# Power_CAN_IO_GPS.net
KiCad netlist of a schematic drawn in Altium Designer
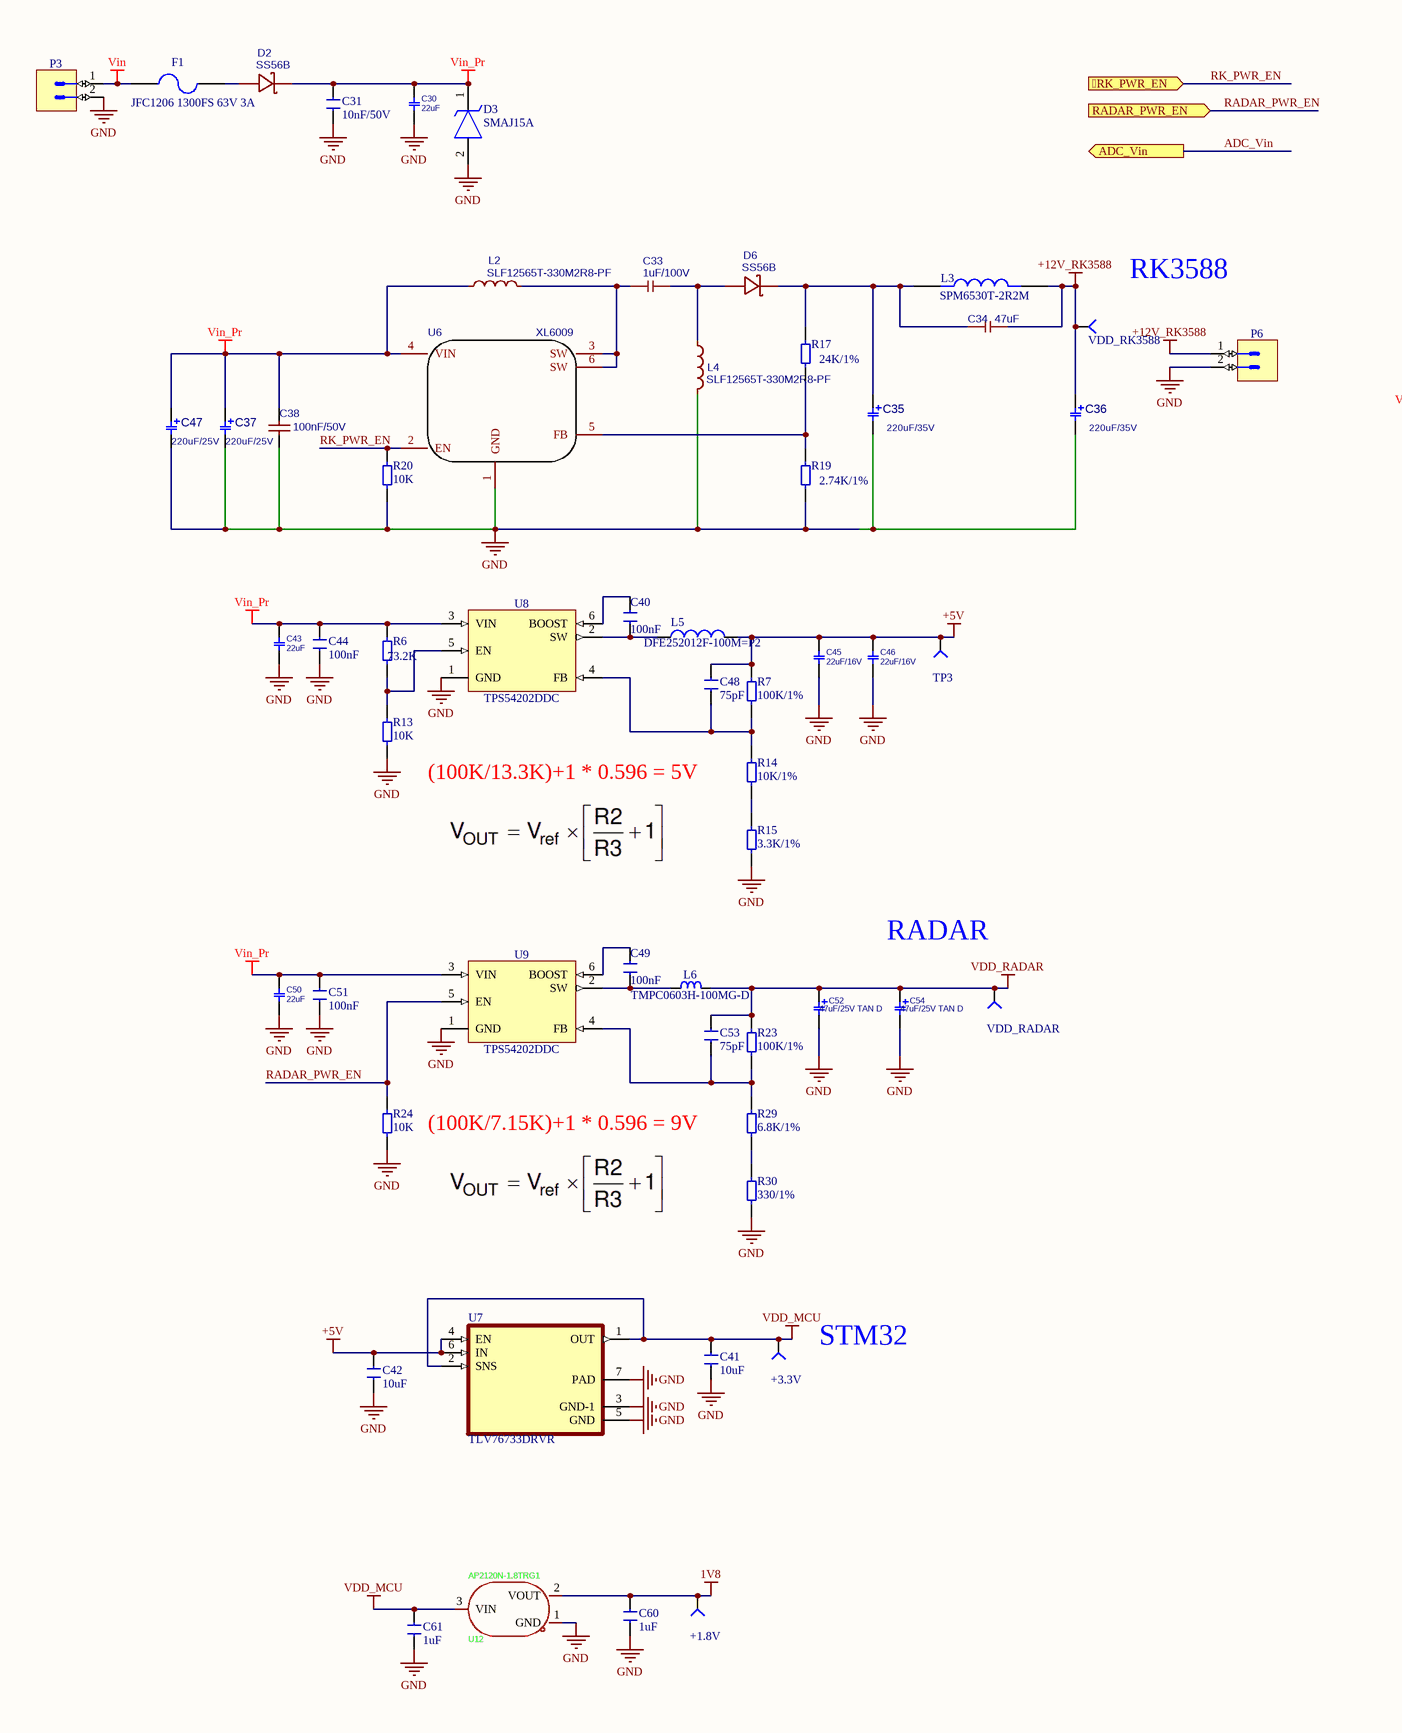
[diagram p0: Power_CAN_IO_GPS.SchDoc, left]
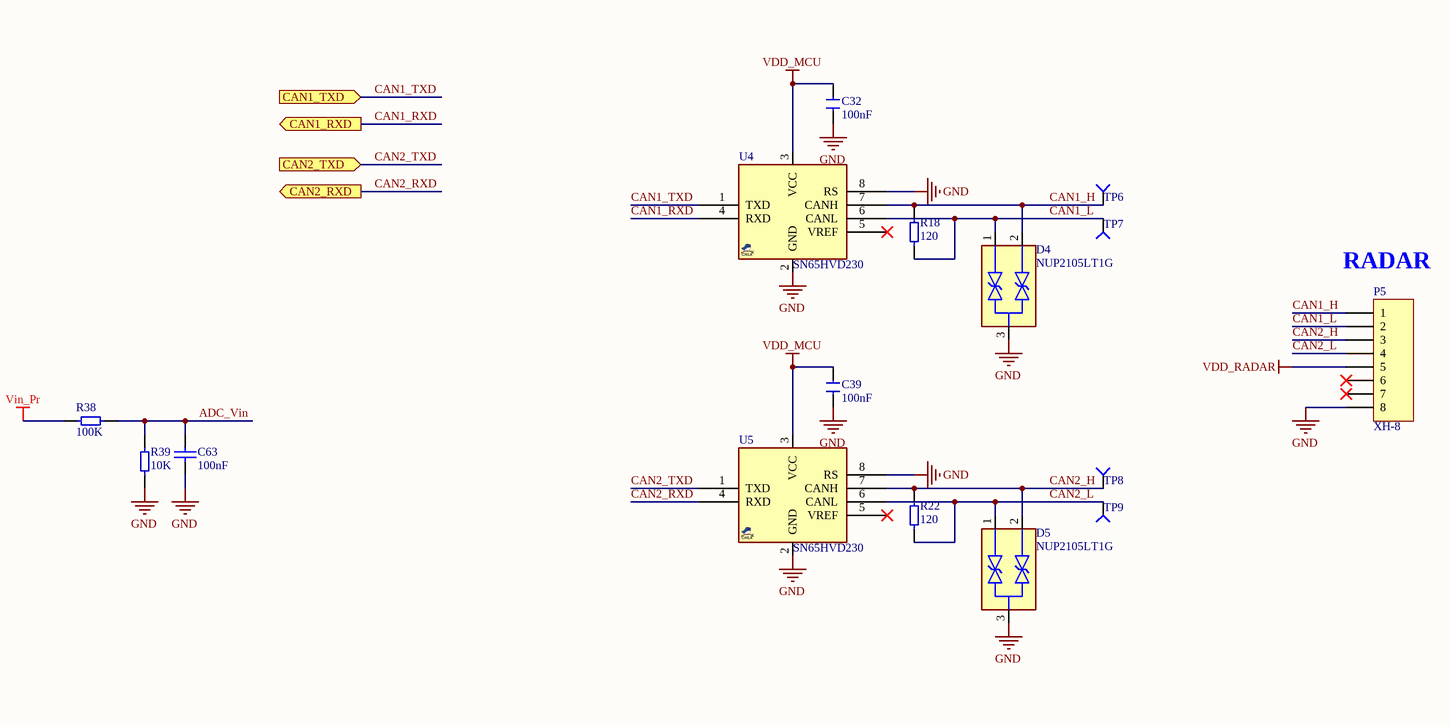
[diagram p1: Power_CAN_IO_GPS.SchDoc, right]

(export (version "E")
  (design (tool "Eeschema 10.0.6"))
  (components
    (comp (ref "+1.8V")
      (value "TEST POINT")
      (footprint "TEST_POINT")
      (libsource (lib "Tracker_MAIN_V1.01") (part "TEST POINT"))
    )
    (comp (ref "+3.3V")
      (value "TEST POINT")
      (footprint "TEST_POINT")
      (libsource (lib "Tracker_MAIN_V1.01") (part "TEST POINT"))
    )
    (comp (ref "C30")
      (value "22uF")
      (footprint "C1206E")
      (description "CAP, MLCC, X5R 22uF 25V 20% 1206")
      (fields (field (name "MANF_P#") "TMK316BBJ226ML-T") (field (name "MANF") "Taiyo Yuden"))
      (libsource (lib "mlcc_smd_passive") (part "CAP_SMD_MLCC_22u25V"))
    )
    (comp (ref "C31")
      (value "10nF/50V")
      (footprint "C0603E")
      (libsource (lib "Rahimi librery") (part "Capacitor SMD"))
    )
    (comp (ref "C32")
      (value "100nF")
      (footprint "C0603E")
      (libsource (lib "Rahimi librery") (part "Capacitor SMD"))
    )
    (comp (ref "C33")
      (value "1uF/100V")
      (footprint "C1210")
      (fields (field (name "MANUFACTURER PART") "GRM32ER71A476ME15L"))
      (libsource (lib "altium-import") (part "root_0_47uF_"))
    )
    (comp (ref "C34")
      (value "47uF")
      (footprint "C1210")
      (fields (field (name "MANUFACTURER PART") "GRM32ER71A476ME15L"))
      (libsource (lib "altium-import") (part "root_0_47uF_"))
    )
    (comp (ref "C35")
      (value "220uF/35V")
      (footprint "C_EL_D8L10")
      (description "CAP, SMD, ELEC,")
      (fields (field (name "MANF_P#") "MANF_PART#") (field (name "MANF") "MANF"))
      (libsource (lib "passive_smd") (part "CAP_SMD_EL_220uF_35v"))
    )
    (comp (ref "C36")
      (value "220uF/35V")
      (footprint "C_EL_D8L10")
      (description "CAP, SMD, ELEC,")
      (fields (field (name "MANF_P#") "MANF_PART#") (field (name "MANF") "MANF"))
      (libsource (lib "passive_smd") (part "CAP_SMD_EL_220uF_35v"))
    )
    (comp (ref "C37")
      (value "220uF/25V")
      (footprint "C_EL_D8L10")
      (description "CAP, SMD, ELEC,")
      (fields (field (name "MANF_P#") "MANF_PART#") (field (name "MANF") "MANF"))
      (libsource (lib "passive_smd") (part "CAP_SMD_EL_220uF_35v"))
    )
    (comp (ref "C38")
      (value "100nF/50V")
      (footprint "C0805")
      (fields (field (name "MANUFACTURER") "FH") (field (name "MANUFACTURER PART") "0805F224M500NT"))
      (libsource (lib "altium-import") (part "root_1_224_"))
    )
    (comp (ref "C39")
      (value "100nF")
      (footprint "C0603E")
      (libsource (lib "Rahimi librery") (part "Capacitor SMD"))
    )
    (comp (ref "C40")
      (value "100nF")
      (footprint "C0603E")
      (libsource (lib "Rahimi librery") (part "Capacitor SMD"))
    )
    (comp (ref "C41")
      (value "10uF")
      (footprint "C0603E")
      (libsource (lib "Rahimi librery") (part "Capacitor SMD"))
    )
    (comp (ref "C42")
      (value "10uF")
      (footprint "C0603E")
      (libsource (lib "Rahimi librery") (part "Capacitor SMD"))
    )
    (comp (ref "C43")
      (value "22uF")
      (footprint "C1206E")
      (description "CAP, MLCC, X5R 22uF 25V 20% 1206")
      (fields (field (name "MANF_P#") "TMK316BBJ226ML-T") (field (name "MANF") "Taiyo Yuden"))
      (libsource (lib "mlcc_smd_passive") (part "CAP_SMD_MLCC_22u25V"))
    )
    (comp (ref "C44")
      (value "100nF")
      (footprint "C0603E")
      (libsource (lib "Rahimi librery") (part "Capacitor SMD"))
    )
    (comp (ref "C45")
      (value "22uF/16V")
      (footprint "C1206E")
      (description "CAP, MLCC, X5R 22uF 25V 20% 1206")
      (fields (field (name "MANF_P#") "TMK316BBJ226ML-T") (field (name "MANF") "Taiyo Yuden"))
      (libsource (lib "mlcc_smd_passive") (part "CAP_SMD_MLCC_22u25V"))
    )
    (comp (ref "C46")
      (value "22uF/16V")
      (footprint "C1206E")
      (description "CAP, MLCC, X5R 22uF 25V 20% 1206")
      (fields (field (name "MANF_P#") "TMK316BBJ226ML-T") (field (name "MANF") "Taiyo Yuden"))
      (libsource (lib "mlcc_smd_passive") (part "CAP_SMD_MLCC_22u25V"))
    )
    (comp (ref "C47")
      (value "220uF/25V")
      (footprint "C_EL_D8L10")
      (description "CAP, SMD, ELEC,")
      (fields (field (name "MANF_P#") "MANF_PART#") (field (name "MANF") "MANF"))
      (libsource (lib "passive_smd") (part "CAP_SMD_EL_220uF_35v"))
    )
    (comp (ref "C48")
      (value "75pF")
      (footprint "C0603E")
      (libsource (lib "Rahimi librery") (part "Capacitor SMD"))
    )
    (comp (ref "C49")
      (value "100nF")
      (footprint "C0603E")
      (libsource (lib "Rahimi librery") (part "Capacitor SMD"))
    )
    (comp (ref "C50")
      (value "22uF")
      (footprint "C1206E")
      (description "CAP, MLCC, X5R 22uF 25V 20% 1206")
      (fields (field (name "MANF_P#") "TMK316BBJ226ML-T") (field (name "MANF") "Taiyo Yuden"))
      (libsource (lib "mlcc_smd_passive") (part "CAP_SMD_MLCC_22u25V"))
    )
    (comp (ref "C51")
      (value "100nF")
      (footprint "C0603E")
      (libsource (lib "Rahimi librery") (part "Capacitor SMD"))
    )
    (comp (ref "C52")
      (value "47uF/25V TAN D")
      (footprint "C_TN_7343")
      (description "CAP, SMD, TAN")
      (fields (field (name "MANF") "VISHAY") (field (name "MANF_P#") "T55A106M6R3C0300"))
      (libsource (lib "passive_smd") (part "CAP_SMD_TAN"))
    )
    (comp (ref "C53")
      (value "75pF")
      (footprint "C0603E")
      (libsource (lib "Rahimi librery") (part "Capacitor SMD"))
    )
    (comp (ref "C54")
      (value "47uF/25V TAN D")
      (footprint "C_TN_7343")
      (description "CAP, SMD, TAN")
      (fields (field (name "MANF") "VISHAY") (field (name "MANF_P#") "T55A106M6R3C0300"))
      (libsource (lib "passive_smd") (part "CAP_SMD_TAN"))
    )
    (comp (ref "C60")
      (value "1uF")
      (footprint "C0603E")
      (libsource (lib "Rahimi librery") (part "Capacitor SMD"))
    )
    (comp (ref "C61")
      (value "1uF")
      (footprint "C0603E")
      (libsource (lib "Rahimi librery") (part "Capacitor SMD"))
    )
    (comp (ref "C63")
      (value "100nF")
      (footprint "C0603")
      (fields (field (name "PUBLISHER") "Altium Limited"))
      (libsource (lib "Miscellaneous Devices") (part "CAP"))
    )
    (comp (ref "D2")
      (value "SS56B")
      (footprint "SMB_L4.6-W3.6-LS5.3-RD")
      (description "40V 5A Schottky Rectifier")
      (fields
        (field (name "MANUFACTURER") "LGE(鲁光)")
        (field (name "MANUFACTURER PART") "SS54")
        (field (name "CONTRIBUTOR") "LCSC")
      )
      (libsource (lib "altium-import") (part "root_2_SS54C_"))
    )
    (comp (ref "D3")
      (value "SMAJ15A")
      (footprint "DIOM5026X229N")
      (description "TVS Diode (Uni-directional)")
      (fields
        (field (name "MANUFACTURER_PART_NUMBER") "SMAJ24A")
        (field (name "MOUSER PART NUMBER") "576-SMAJ24A")
      )
      (libsource (lib "*") (part "SMAJ24A"))
    )
    (comp (ref "D4")
      (value "NUP2105LT1G")
      (footprint "SOT95P237X111-3N")
      (description "Dual Bi-Directional TVS Diode 350W 3-Pin SOT-23 ¦ ON Semiconductor NUP2105LT1G")
      (fields (field (name "MF") "ON Semiconductor"))
      (libsource (lib "NUP2105LT1G") (part "NUP2105LT1G"))
    )
    (comp (ref "D5")
      (value "NUP2105LT1G")
      (footprint "SOT95P237X111-3N")
      (description "Dual Bi-Directional TVS Diode 350W 3-Pin SOT-23 ¦ ON Semiconductor NUP2105LT1G")
      (fields (field (name "MF") "ON Semiconductor"))
      (libsource (lib "NUP2105LT1G") (part "NUP2105LT1G"))
    )
    (comp (ref "D6")
      (value "SS56B")
      (footprint "SMB_L4.6-W3.6-LS5.3-RD")
      (description "40V 5A Schottky Rectifier")
      (fields
        (field (name "MANUFACTURER") "LGE(鲁光)")
        (field (name "MANUFACTURER PART") "SS54")
        (field (name "CONTRIBUTOR") "LCSC")
      )
      (libsource (lib "altium-import") (part "root_2_SS54C_"))
    )
    (comp (ref "F1")
      (value "JFC1206 1300FS 63V 3A")
      (footprint "1206 FUSE")
      (description "Fuse Type Fast Acting with 63V, 3A, 1206")
      (fields (field (name "DESIGNER") "Abbas Basereh"))
      (libsource (lib "altium-import") (part "root_0_Fuse SMD1206_"))
    )
    (comp (ref "L2")
      (value "SLF12565T-330M2R8-PF")
      (footprint "IND-SMD_L12.3-W12.3")
      (fields
        (field (name "MANUFACTURER") "SHOU HAN(首韩)")
        (field (name "MANUFACTURER PART") "CYH125-33UH")
        (field (name "CONTRIBUTOR") "lcsc")
      )
      (libsource (lib "altium-import") (part "root_0_33uH_"))
    )
    (comp (ref "L3")
      (value "SPM6530T-2R2M")
      (footprint "IND_SPM6530T-2R2M-HZ")
      (fields
        (field (name "MP") "SPM6530T-2R2M-HZ")
        (field (name "MF") "{'manufacturer': u'TDK Corporation'}")
      )
      (libsource (lib "SPM6530T-2R2M-HZ") (part "SPM6530T-2R2M-HZ"))
    )
    (comp (ref "L4")
      (value "SLF12565T-330M2R8-PF")
      (footprint "IND-SMD_L12.3-W12.3")
      (fields
        (field (name "MANUFACTURER") "SHOU HAN(首韩)")
        (field (name "MANUFACTURER PART") "CYH125-33UH")
        (field (name "CONTRIBUTOR") "lcsc")
      )
      (libsource (lib "altium-import") (part "root_3_33uH_"))
    )
    (comp (ref "L5")
      (value "DFE252012F-100M=P2")
      (footprint "INDC2520X120N")
      (description "Inductor with Inductance: 10uH Tol. +/-20%, Package: 1008 (2520)")
      (fields (field (name "MF") "Murata Electronics") (field (name "DIGI-KEY_PART_NUMBER") "490-13050-1-ND"))
      (libsource (lib "DFE252012F-100M_P2") (part "DFE252012F-100M=P2"))
    )
    (comp (ref "L6")
      (value "TMPC0603H-100MG-D")
      (footprint "IND-SMD_L7.3-W6.6")
      (description "Inductor")
      (fields
        (field (name "PART NUMBER") "IND1008_1UH_20%_WURTH_74479787210B")
        (field (name "POWER") "1.95A")
        (field (name "AUTHOR") "CERN DEM JLC")
      )
      (libsource (lib "Inductors & Transformers") (part "Inductor"))
    )
    (comp (ref "P3")
      (value "KF2EDGV+K-3.81-2P")
      (footprint "PHOENIX_1803426")
      (description "Connector 2 Male")
      (fields
        (field (name "PART NUMBER") "PHOENIX_1803426")
        (field (name "MANUFACTURER") "PHOENIX CONTACT")
        (field (name "AUTHOR") "CERN DEM JLC")
      )
      (libsource (lib "Connectors") (part "Connector 2 Male"))
    )
    (comp (ref "P5")
      (value "XH-8")
      (footprint "HDR1X8")
      (description "Header, 8-Pin")
      (fields (field (name "PUBLISHER") "Altium Limited"))
      (libsource (lib "Miscellaneous Connectors") (part "Header 8"))
    )
    (comp (ref "P6")
      (value "KF2EDGV+K-3.81-2P")
      (footprint "PHOENIX_1803426")
      (description "Connector 2 Male")
      (fields
        (field (name "PART NUMBER") "PHOENIX_1803426")
        (field (name "MANUFACTURER") "PHOENIX CONTACT")
        (field (name "AUTHOR") "CERN DEM JLC")
      )
      (libsource (lib "") (part "Connector 2 Male_1"))
    )
    (comp (ref "R6")
      (value "73.2K")
      (footprint "R0603E")
      (libsource (lib "Rahimi librery") (part "Resistor SMD"))
    )
    (comp (ref "R7")
      (value "100K/1%")
      (footprint "R0603E")
      (libsource (lib "Rahimi librery") (part "Resistor SMD"))
    )
    (comp (ref "R13")
      (value "10K")
      (footprint "R0603E")
      (libsource (lib "Rahimi librery") (part "Resistor SMD"))
    )
    (comp (ref "R14")
      (value "10K/1%")
      (footprint "R0603E")
      (libsource (lib "Rahimi librery") (part "Resistor SMD"))
    )
    (comp (ref "R15")
      (value "3.3K/1%")
      (footprint "R0603E")
      (libsource (lib "Rahimi librery") (part "Resistor SMD"))
    )
    (comp (ref "R17")
      (value "24K/1%")
      (footprint "R0603E")
      (libsource (lib "Rahimi librery") (part "Resistor SMD"))
    )
    (comp (ref "R18")
      (value "120")
      (footprint "R0603E")
      (libsource (lib "Rahimi librery") (part "Resistor SMD"))
    )
    (comp (ref "R19")
      (value "2.74K/1%")
      (footprint "R0603E")
      (libsource (lib "Rahimi librery") (part "Resistor SMD"))
    )
    (comp (ref "R20")
      (value "10K")
      (footprint "R0603E")
      (libsource (lib "Rahimi librery") (part "Resistor SMD"))
    )
    (comp (ref "R22")
      (value "120")
      (footprint "R0603E")
      (libsource (lib "Rahimi librery") (part "Resistor SMD"))
    )
    (comp (ref "R23")
      (value "100K/1%")
      (footprint "R0603E")
      (libsource (lib "Rahimi librery") (part "Resistor SMD"))
    )
    (comp (ref "R24")
      (value "10K")
      (footprint "R0603E")
      (libsource (lib "Rahimi librery") (part "Resistor SMD"))
    )
    (comp (ref "R29")
      (value "6.8K/1%")
      (footprint "R0603E")
      (libsource (lib "Rahimi librery") (part "Resistor SMD"))
    )
    (comp (ref "R30")
      (value "330/1%")
      (footprint "R0603E")
      (libsource (lib "Rahimi librery") (part "Resistor SMD"))
    )
    (comp (ref "R38")
      (value "100K")
      (footprint "R0603")
      (libsource (lib "Rahimi librery") (part "Resistor SMD"))
    )
    (comp (ref "R39")
      (value "10K")
      (footprint "R0603")
      (libsource (lib "Rahimi librery") (part "Resistor SMD"))
    )
    (comp (ref "TP3")
      (value "TEST POINT")
      (footprint "TEST_POINT")
      (libsource (lib "Tracker_MAIN_V1.01") (part "TEST POINT"))
    )
    (comp (ref "TP6")
      (value "TEST POINT")
      (footprint "TEST_POINT")
      (libsource (lib "Tracker_MAIN_V1.01") (part "TEST POINT"))
    )
    (comp (ref "TP7")
      (value "TEST POINT")
      (footprint "TEST_POINT")
      (libsource (lib "Tracker_MAIN_V1.01") (part "TEST POINT"))
    )
    (comp (ref "TP8")
      (value "TEST POINT")
      (footprint "TEST_POINT")
      (libsource (lib "Tracker_MAIN_V1.01") (part "TEST POINT"))
    )
    (comp (ref "TP9")
      (value "TEST POINT")
      (footprint "TEST_POINT")
      (libsource (lib "Tracker_MAIN_V1.01") (part "TEST POINT"))
    )
    (comp (ref "U4")
      (value "SN65HVD230")
      (footprint "SO_8")
      (description "CAN,  Transceivers, 3.3V (VDD)")
      (fields (field (name "MANF") "Texas Instruments") (field (name "MANF_P#") "SN65HVD230D, SN65HVD230QD"))
      (libsource (lib "can_phy") (part "SN65HVD230_SOP8"))
    )
    (comp (ref "U5")
      (value "SN65HVD230")
      (footprint "SO_8")
      (description "CAN,  Transceivers, 3.3V (VDD)")
      (fields (field (name "MANF") "Texas Instruments") (field (name "MANF_P#") "SN65HVD230D, SN65HVD230QD"))
      (libsource (lib "can_phy") (part "SN65HVD230_SOP8"))
    )
    (comp (ref "U6")
      (value "XL6009")
      (footprint "TO-263-5")
      (fields (field (name "MANUFACTURER") "XLSEMI") (field (name "CONTRIBUTOR") "GerryChen"))
      (libsource (lib "NewSpeedRadar_Board") (part "XL6009"))
    )
    (comp (ref "U7")
      (value "TLV76733DRVR")
      (footprint "SON65P200X200X80-7N")
      (description "Adjustable- and fixed-output, 1-A, 16-V, positive-voltage low-dropout (LDO) linear regulator")
      (fields (field (name "MF") "Texas Instruments"))
      (libsource (lib "NewSpeedRadar_Board") (part "TLV76733DRVR"))
    )
    (comp (ref "U8")
      (value "TPS54202DDC")
      (footprint "SOT95P280X100-6N")
      (description "4.5V to 28V Input, 2-A Output, EMI Friendly\r\nSynchronous Step Down Converter")
      (fields (field (name "MANUFACTURER") "TEXAS INSTRUMENTS") (field (name "AUTHOR") "CERN DEM HF"))
      (libsource (lib "ICs And Semiconductors") (part "TPS54202"))
    )
    (comp (ref "U9")
      (value "TPS54202DDC")
      (footprint "SOT95P280X100-6N")
      (description "4.5V to 28V Input, 2-A Output, EMI Friendly\r\nSynchronous Step Down Converter")
      (fields (field (name "MANUFACTURER") "TEXAS INSTRUMENTS") (field (name "AUTHOR") "CERN DEM HF"))
      (libsource (lib "ICs And Semiconductors") (part "TPS54202"))
    )
    (comp (ref "U12")
      (value "AP2120N-1.8TRG1")
      (footprint "SOT-23-3_L2.9-W1.3-P1.90-LS2.4-BR")
      (fields (field (name "MANUFACTURER") "DIODES(美台)") (field (name "MANUFACTURER PART") "AP2120N-3.3TRG1"))
      (libsource (lib "altium-import") (part "root_1_AP2120N-3.3TRG1_"))
    )
    (comp (ref "VDD_RADAR")
      (value "TEST POINT")
      (footprint "TEST_POINT")
      (libsource (lib "Tracker_MAIN_V1.01") (part "TEST POINT"))
    )
    (comp (ref "VDD_RK3588")
      (value "TEST POINT")
      (footprint "TEST_POINT")
      (libsource (lib "Tracker_MAIN_V1.01") (part "TEST POINT"))
    )
  )
  (nets
    (net (code "1") (name "+5V") (class "Default")
      (node (ref "C42") (pin "2") (pintype "passive"))
      (node (ref "C45") (pin "2") (pinfunction "2_2") (pintype "passive"))
      (node (ref "C46") (pin "2") (pinfunction "2_2") (pintype "passive"))
      (node (ref "C48") (pin "2") (pintype "passive"))
      (node (ref "L5") (pin "2") (pinfunction "2_2") (pintype "passive"))
      (node (ref "R7") (pin "1") (pintype "passive"))
      (node (ref "TP3") (pin "1") (pinfunction "TP_1") (pintype "passive"))
      (node (ref "U7") (pin "4") (pinfunction "EN_4") (pintype "input"))
      (node (ref "U7") (pin "6") (pinfunction "IN_6") (pintype "input"))
    )
    (net (code "2") (name "+12V_RK3588") (class "Default")
      (node (ref "C34") (pin "2") (pinfunction "2_2") (pintype "passive"))
      (node (ref "C36") (pin "1") (pinfunction "1_1") (pintype "passive"))
      (node (ref "L3") (pin "2") (pinfunction "2_2") (pintype "passive"))
      (node (ref "P6") (pin "1") (pinfunction "1_1") (pintype "bidirectional"))
      (node (ref "VDD_RK3588") (pin "1") (pinfunction "TP_1") (pintype "passive"))
    )
    (net (code "3") (name "/ADC_Vin") (class "Default")
      (node (ref "C63") (pin "2") (pinfunction "2_2") (pintype "passive"))
      (node (ref "R38") (pin "2") (pintype "passive"))
      (node (ref "R39") (pin "2") (pintype "passive"))
    )
    (net (code "4") (name "/CAN1_H") (class "Default")
      (node (ref "D4") (pin "2") (pinfunction "2_2") (pintype "passive"))
      (node (ref "P5") (pin "1") (pinfunction "1_1") (pintype "passive"))
      (node (ref "R18") (pin "2") (pintype "passive"))
      (node (ref "TP6") (pin "1") (pinfunction "TP_1") (pintype "passive"))
      (node (ref "U4") (pin "7") (pinfunction "CANH_7") (pintype "passive"))
    )
    (net (code "5") (name "/CAN1_L") (class "Default")
      (node (ref "D4") (pin "1") (pinfunction "1_1") (pintype "passive"))
      (node (ref "P5") (pin "2") (pinfunction "2_2") (pintype "passive"))
      (node (ref "R18") (pin "1") (pintype "passive"))
      (node (ref "TP7") (pin "1") (pinfunction "TP_1") (pintype "passive"))
      (node (ref "U4") (pin "6") (pinfunction "CANL_6") (pintype "passive"))
    )
    (net (code "6") (name "/CAN1_RXD") (class "Default")
      (node (ref "U4") (pin "4") (pinfunction "RXD_4") (pintype "passive"))
    )
    (net (code "7") (name "/CAN1_TXD") (class "Default")
      (node (ref "U4") (pin "1") (pinfunction "TXD_1") (pintype "passive"))
    )
    (net (code "8") (name "/CAN2_H") (class "Default")
      (node (ref "D5") (pin "2") (pinfunction "2_2") (pintype "passive"))
      (node (ref "P5") (pin "3") (pinfunction "3_3") (pintype "passive"))
      (node (ref "R22") (pin "2") (pintype "passive"))
      (node (ref "TP8") (pin "1") (pinfunction "TP_1") (pintype "passive"))
      (node (ref "U5") (pin "7") (pinfunction "CANH_7") (pintype "passive"))
    )
    (net (code "9") (name "/CAN2_L") (class "Default")
      (node (ref "D5") (pin "1") (pinfunction "1_1") (pintype "passive"))
      (node (ref "P5") (pin "4") (pinfunction "4_4") (pintype "passive"))
      (node (ref "R22") (pin "1") (pintype "passive"))
      (node (ref "TP9") (pin "1") (pinfunction "TP_1") (pintype "passive"))
      (node (ref "U5") (pin "6") (pinfunction "CANL_6") (pintype "passive"))
    )
    (net (code "10") (name "/CAN2_RXD") (class "Default")
      (node (ref "U5") (pin "4") (pinfunction "RXD_4") (pintype "passive"))
    )
    (net (code "11") (name "/CAN2_TXD") (class "Default")
      (node (ref "U5") (pin "1") (pinfunction "TXD_1") (pintype "passive"))
    )
    (net (code "12") (name "/RADAR_PWR_EN") (class "Default")
      (node (ref "R24") (pin "1") (pintype "passive"))
      (node (ref "U9") (pin "5") (pinfunction "EN_5") (pintype "input"))
    )
    (net (code "13") (name "/RK_PWR_EN") (class "Default")
      (node (ref "R20") (pin "1") (pintype "passive"))
      (node (ref "U6") (pin "2") (pinfunction "EN_2") (pintype "passive"))
    )
    (net (code "14") (name "1V8") (class "Default")
      (node (ref "+1.8V") (pin "1") (pinfunction "TP_1") (pintype "passive"))
      (node (ref "C60") (pin "2") (pintype "passive"))
      (node (ref "U12") (pin "2") (pinfunction "VOUT_2") (pintype "passive"))
    )
    (net (code "15") (name "GND") (class "Default")
      (node (ref "C30") (pin "1") (pinfunction "1_1") (pintype "passive"))
      (node (ref "C31") (pin "1") (pintype "passive"))
      (node (ref "C32") (pin "1") (pintype "passive"))
      (node (ref "C35") (pin "2") (pinfunction "2_2") (pintype "passive"))
      (node (ref "C36") (pin "2") (pinfunction "2_2") (pintype "passive"))
      (node (ref "C37") (pin "2") (pinfunction "2_2") (pintype "passive"))
      (node (ref "C38") (pin "1") (pinfunction "1_1") (pintype "passive"))
      (node (ref "C39") (pin "1") (pintype "passive"))
      (node (ref "C41") (pin "1") (pintype "passive"))
      (node (ref "C42") (pin "1") (pintype "passive"))
      (node (ref "C43") (pin "1") (pinfunction "1_1") (pintype "passive"))
      (node (ref "C44") (pin "1") (pintype "passive"))
      (node (ref "C45") (pin "1") (pinfunction "1_1") (pintype "passive"))
      (node (ref "C46") (pin "1") (pinfunction "1_1") (pintype "passive"))
      (node (ref "C47") (pin "2") (pinfunction "2_2") (pintype "passive"))
      (node (ref "C50") (pin "1") (pinfunction "1_1") (pintype "passive"))
      (node (ref "C51") (pin "1") (pintype "passive"))
      (node (ref "C52") (pin "2") (pinfunction "2_2") (pintype "passive"))
      (node (ref "C54") (pin "2") (pinfunction "2_2") (pintype "passive"))
      (node (ref "C60") (pin "1") (pintype "passive"))
      (node (ref "C61") (pin "1") (pintype "passive"))
      (node (ref "C63") (pin "1") (pinfunction "1_1") (pintype "passive"))
      (node (ref "D3") (pin "2") (pinfunction "A_2") (pintype "passive"))
      (node (ref "D4") (pin "3") (pinfunction "3_3") (pintype "passive"))
      (node (ref "D5") (pin "3") (pinfunction "3_3") (pintype "passive"))
      (node (ref "L4") (pin "2") (pinfunction "2_2") (pintype "passive"))
      (node (ref "P3") (pin "2") (pinfunction "2_2") (pintype "bidirectional"))
      (node (ref "P5") (pin "8") (pinfunction "8_8") (pintype "passive"))
      (node (ref "P6") (pin "2") (pinfunction "2_2") (pintype "bidirectional"))
      (node (ref "R13") (pin "2") (pintype "passive"))
      (node (ref "R15") (pin "2") (pintype "passive"))
      (node (ref "R19") (pin "2") (pintype "passive"))
      (node (ref "R20") (pin "2") (pintype "passive"))
      (node (ref "R24") (pin "2") (pintype "passive"))
      (node (ref "R30") (pin "2") (pintype "passive"))
      (node (ref "R39") (pin "1") (pintype "passive"))
      (node (ref "U12") (pin "1") (pinfunction "GND_1") (pintype "passive"))
      (node (ref "U4") (pin "2") (pinfunction "GND_2") (pintype "passive"))
      (node (ref "U4") (pin "8") (pinfunction "RS_8") (pintype "passive"))
      (node (ref "U5") (pin "2") (pinfunction "GND_2") (pintype "passive"))
      (node (ref "U5") (pin "8") (pinfunction "RS_8") (pintype "passive"))
      (node (ref "U6") (pin "1") (pinfunction "GND_1") (pintype "passive"))
      (node (ref "U7") (pin "3") (pinfunction "GND-1_3") (pintype "power_in"))
      (node (ref "U7") (pin "5") (pinfunction "GND_5") (pintype "power_in"))
      (node (ref "U7") (pin "7") (pinfunction "PAD_7") (pintype "power_in"))
      (node (ref "U8") (pin "1") (pinfunction "GND_1") (pintype "power_in"))
      (node (ref "U9") (pin "1") (pinfunction "GND_1") (pintype "power_in"))
    )
    (net (code "16") (name "Net-(C33-Pad1)") (class "Default")
      (node (ref "C33") (pin "1") (pinfunction "1_1") (pintype "passive"))
      (node (ref "L2") (pin "2") (pinfunction "2_2") (pintype "passive"))
      (node (ref "U6") (pin "3") (pinfunction "SW_3") (pintype "passive"))
      (node (ref "U6") (pin "6") (pinfunction "SW_6") (pintype "passive"))
    )
    (net (code "17") (name "Net-(D2-A)") (class "Default")
      (node (ref "D2") (pin "2") (pinfunction "A_2") (pintype "passive"))
      (node (ref "F1") (pin "2") (pinfunction "2_2") (pintype "passive"))
    )
    (net (code "18") (name "Net-(D6-A)") (class "Default")
      (node (ref "C33") (pin "2") (pinfunction "2_2") (pintype "passive"))
      (node (ref "D6") (pin "2") (pinfunction "A_2") (pintype "passive"))
      (node (ref "L4") (pin "1") (pinfunction "1_1") (pintype "passive"))
    )
    (net (code "19") (name "Net-(D6-K)") (class "Default")
      (node (ref "C34") (pin "1") (pinfunction "1_1") (pintype "passive"))
      (node (ref "C35") (pin "1") (pinfunction "1_1") (pintype "passive"))
      (node (ref "D6") (pin "1") (pinfunction "K_1") (pintype "passive"))
      (node (ref "L3") (pin "1") (pinfunction "1_1") (pintype "passive"))
      (node (ref "R17") (pin "1") (pintype "passive"))
    )
    (net (code "20") (name "Net-(R14-Pad2)") (class "Default")
      (node (ref "R14") (pin "2") (pintype "passive"))
      (node (ref "R15") (pin "1") (pintype "passive"))
    )
    (net (code "21") (name "Net-(R29-Pad2)") (class "Default")
      (node (ref "R29") (pin "2") (pintype "passive"))
      (node (ref "R30") (pin "1") (pintype "passive"))
    )
    (net (code "22") (name "Net-(U6-FB)") (class "Default")
      (node (ref "R17") (pin "2") (pintype "passive"))
      (node (ref "R19") (pin "1") (pintype "passive"))
      (node (ref "U6") (pin "5") (pinfunction "FB_5") (pintype "passive"))
    )
    (net (code "23") (name "Net-(U8-BOOST)") (class "Default")
      (node (ref "C40") (pin "1") (pintype "passive"))
      (node (ref "U8") (pin "6") (pinfunction "BOOST_6") (pintype "input"))
    )
    (net (code "24") (name "Net-(U8-EN)") (class "Default")
      (node (ref "R13") (pin "1") (pintype "passive"))
      (node (ref "R6") (pin "2") (pintype "passive"))
      (node (ref "U8") (pin "5") (pinfunction "EN_5") (pintype "input"))
    )
    (net (code "25") (name "Net-(U8-FB)") (class "Default")
      (node (ref "C48") (pin "1") (pintype "passive"))
      (node (ref "R14") (pin "1") (pintype "passive"))
      (node (ref "R7") (pin "2") (pintype "passive"))
      (node (ref "U8") (pin "4") (pinfunction "FB_4") (pintype "input"))
    )
    (net (code "26") (name "Net-(U8-SW)") (class "Default")
      (node (ref "C40") (pin "2") (pintype "passive"))
      (node (ref "L5") (pin "1") (pinfunction "1_1") (pintype "passive"))
      (node (ref "U8") (pin "2") (pinfunction "SW_2") (pintype "output"))
    )
    (net (code "27") (name "Net-(U9-BOOST)") (class "Default")
      (node (ref "C49") (pin "1") (pintype "passive"))
      (node (ref "U9") (pin "6") (pinfunction "BOOST_6") (pintype "input"))
    )
    (net (code "28") (name "Net-(U9-FB)") (class "Default")
      (node (ref "C53") (pin "1") (pintype "passive"))
      (node (ref "R23") (pin "2") (pintype "passive"))
      (node (ref "R29") (pin "1") (pintype "passive"))
      (node (ref "U9") (pin "4") (pinfunction "FB_4") (pintype "input"))
    )
    (net (code "29") (name "Net-(U9-SW)") (class "Default")
      (node (ref "C49") (pin "2") (pintype "passive"))
      (node (ref "L6") (pin "1") (pinfunction "1_1") (pintype "passive"))
      (node (ref "U9") (pin "2") (pinfunction "SW_2") (pintype "output"))
    )
    (net (code "30") (name "VDD_MCU") (class "Default")
      (node (ref "+3.3V") (pin "1") (pinfunction "TP_1") (pintype "passive"))
      (node (ref "C32") (pin "2") (pintype "passive"))
      (node (ref "C39") (pin "2") (pintype "passive"))
      (node (ref "C41") (pin "2") (pintype "passive"))
      (node (ref "C61") (pin "2") (pintype "passive"))
      (node (ref "U12") (pin "3") (pinfunction "VIN_3") (pintype "passive"))
      (node (ref "U4") (pin "3") (pinfunction "VCC_3") (pintype "passive"))
      (node (ref "U5") (pin "3") (pinfunction "VCC_3") (pintype "passive"))
      (node (ref "U7") (pin "1") (pinfunction "OUT_1") (pintype "output"))
      (node (ref "U7") (pin "2") (pinfunction "SNS_2") (pintype "input"))
    )
    (net (code "31") (name "VDD_RADAR") (class "Default")
      (node (ref "C52") (pin "1") (pinfunction "1_1") (pintype "passive"))
      (node (ref "C53") (pin "2") (pintype "passive"))
      (node (ref "C54") (pin "1") (pinfunction "1_1") (pintype "passive"))
      (node (ref "L6") (pin "2") (pinfunction "2_2") (pintype "passive"))
      (node (ref "P5") (pin "5") (pinfunction "5_5") (pintype "passive"))
      (node (ref "R23") (pin "1") (pintype "passive"))
      (node (ref "VDD_RADAR") (pin "1") (pinfunction "TP_1") (pintype "passive"))
    )
    (net (code "32") (name "Vin") (class "Default")
      (node (ref "F1") (pin "1") (pinfunction "1_1") (pintype "passive"))
      (node (ref "P3") (pin "1") (pinfunction "1_1") (pintype "bidirectional"))
    )
    (net (code "33") (name "Vin_Pr") (class "Default")
      (node (ref "C30") (pin "2") (pinfunction "2_2") (pintype "passive"))
      (node (ref "C31") (pin "2") (pintype "passive"))
      (node (ref "C37") (pin "1") (pinfunction "1_1") (pintype "passive"))
      (node (ref "C38") (pin "2") (pinfunction "2_2") (pintype "passive"))
      (node (ref "C43") (pin "2") (pinfunction "2_2") (pintype "passive"))
      (node (ref "C44") (pin "2") (pintype "passive"))
      (node (ref "C47") (pin "1") (pinfunction "1_1") (pintype "passive"))
      (node (ref "C50") (pin "2") (pinfunction "2_2") (pintype "passive"))
      (node (ref "C51") (pin "2") (pintype "passive"))
      (node (ref "D2") (pin "1") (pinfunction "K_1") (pintype "passive"))
      (node (ref "D3") (pin "1") (pinfunction "K_1") (pintype "passive"))
      (node (ref "L2") (pin "1") (pinfunction "1_1") (pintype "passive"))
      (node (ref "R38") (pin "1") (pintype "passive"))
      (node (ref "R6") (pin "1") (pintype "passive"))
      (node (ref "U6") (pin "4") (pinfunction "VIN_4") (pintype "passive"))
      (node (ref "U8") (pin "3") (pinfunction "VIN_3") (pintype "input"))
      (node (ref "U9") (pin "3") (pinfunction "VIN_3") (pintype "input"))
    )
    (net (code "34") (name "unconnected-(P5-Pad6)") (class "Default")
      (node (ref "P5") (pin "6") (pinfunction "6_6") (pintype "passive+no_connect"))
    )
    (net (code "35") (name "unconnected-(P5-Pad7)") (class "Default")
      (node (ref "P5") (pin "7") (pinfunction "7_7") (pintype "passive+no_connect"))
    )
    (net (code "36") (name "unconnected-(U4-VREF-Pad5)") (class "Default")
      (node (ref "U4") (pin "5") (pinfunction "VREF_5") (pintype "passive+no_connect"))
    )
    (net (code "37") (name "unconnected-(U5-VREF-Pad5)") (class "Default")
      (node (ref "U5") (pin "5") (pinfunction "VREF_5") (pintype "passive+no_connect"))
    )
  )
)
